# 3_-_SRAM.net
KiCad netlist of a schematic drawn in Altium Designer
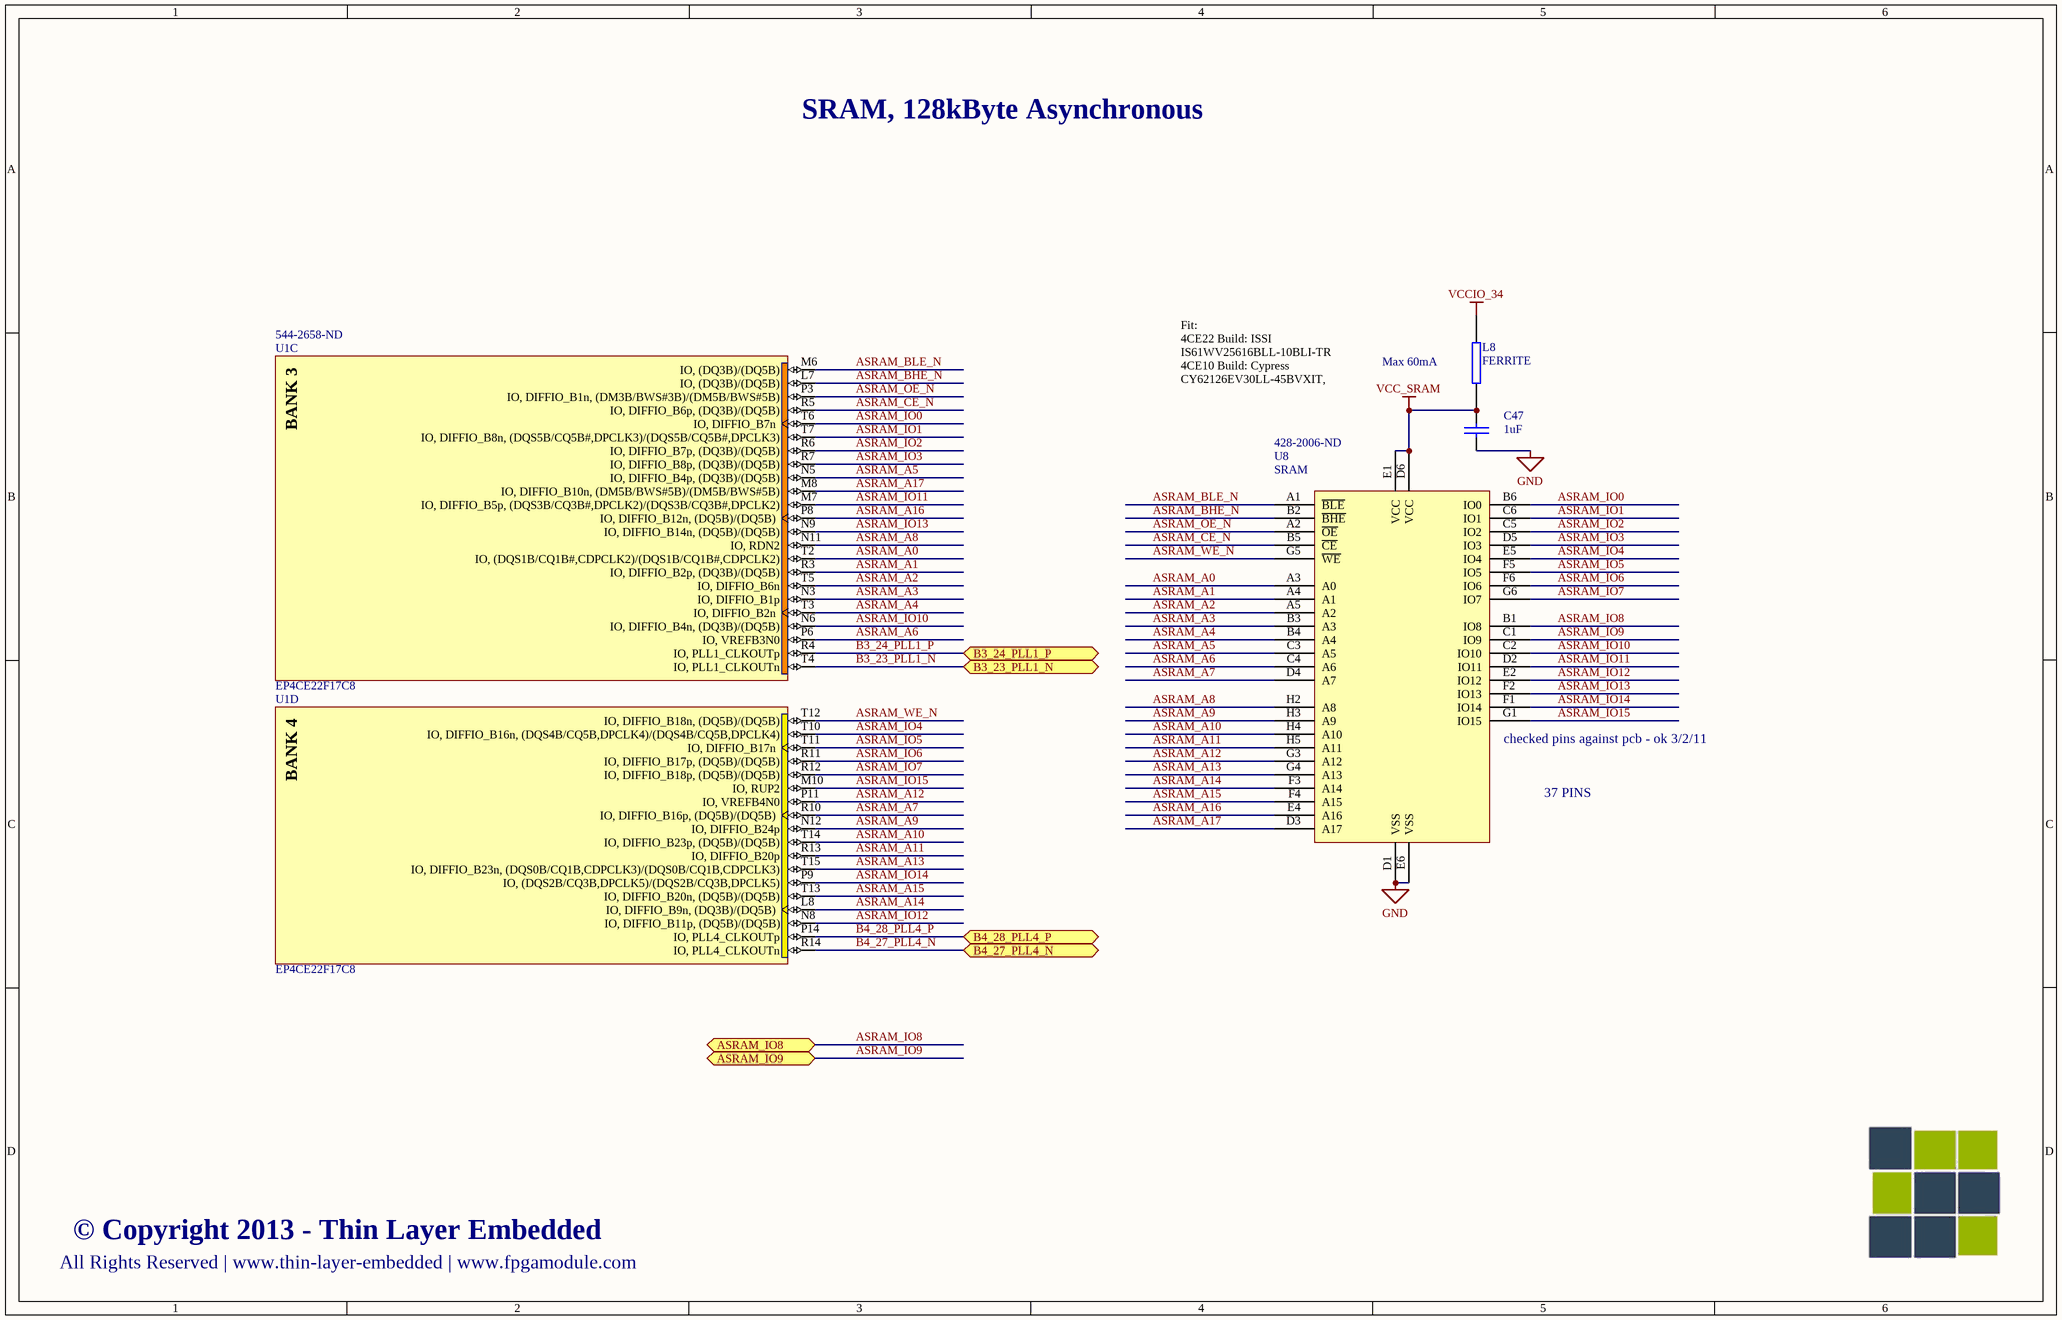
[diagram p0: 3 - SRAM.SchDoc]

(export (version "E")
  (design (tool "Eeschema 10.0.6"))
  (components
    (comp (ref "C47")
      (value "1uF")
      (footprint "0402_HD")
      (description "Capacitor")
      (fields
        (field (name "MANUFACTURER") "Yageo")
        (field (name "MANUFACTURER PART NUMBER") "CC0402ZRY5V8BB104")
      )
      (libsource (lib "*") (part "CAP"))
    )
    (comp (ref "L8") (value "FERRITE") (footprint "0402_HD") (libsource (lib "*") (part "FERRITE")))
    (comp (ref "U1")
      (value "EP4CE22F17C8")
      (footprint "FBGA256")
      (description "IC CYCLONE IV E FPGA 22K 256FBGA")
      (fields
        (field (name "SUPPLIER PART NUMBER 1") "544-2658-ND")
        (field (name "MANUFACTURER") "Altera")
        (field (name "MANUFACTURER PART NUMBER") "EP4CE22F17C7N")
        (field (name "PUBLISHER") "Altium Limited")
      )
      (libsource (lib "OB_EP4CE15E22") (part "EP4CE22F17C8"))
    )
    (comp (ref "U8")
      (value "SRAM")
      (footprint "VFBGA48")
      (description "IC SRAM 1MBIT 10NS 48VFBGA")
      (fields
        (field (name "SUPPLIER PART NUMBER 1") "428-2006-ND")
        (field (name "MANUFACTURER") "Cypress Semiconductor Corp")
        (field (name "MANUFACTURER PART NUMBER") "CY7C1021DV33-10BVXI")
      )
      (libsource (lib "OB_EP4CE15E22") (part "CY7C1021DV331"))
    )
  )
  (nets
    (net (code "1") (name "/ASRAM_A0") (class "Default")
      (node (ref "U1") (pin "T2") (pinfunction "IO,_(DQS1B/CQ1B#,CDPCLK2)/(DQS1B/CQ1B#,CDPCLK2)_T2") (pintype "bidirectional"))
      (node (ref "U8") (pin "A3") (pinfunction "A0_A3") (pintype "passive"))
    )
    (net (code "2") (name "/ASRAM_A1") (class "Default")
      (node (ref "U1") (pin "R3") (pinfunction "IO,_DIFFIO_B2p,_(DQ3B)/(DQ5B)_R3") (pintype "bidirectional"))
      (node (ref "U8") (pin "A4") (pinfunction "A1_A4") (pintype "passive"))
    )
    (net (code "3") (name "/ASRAM_A2") (class "Default")
      (node (ref "U1") (pin "T5") (pinfunction "IO,_DIFFIO_B6n_T5") (pintype "bidirectional"))
      (node (ref "U8") (pin "A5") (pinfunction "A2_A5") (pintype "passive"))
    )
    (net (code "4") (name "/ASRAM_A3") (class "Default")
      (node (ref "U1") (pin "N3") (pinfunction "IO,_DIFFIO_B1p_N3") (pintype "bidirectional"))
      (node (ref "U8") (pin "B3") (pinfunction "A3_B3") (pintype "passive"))
    )
    (net (code "5") (name "/ASRAM_A4") (class "Default")
      (node (ref "U1") (pin "T3") (pinfunction "IO,_DIFFIO_B2n_T3") (pintype "bidirectional"))
      (node (ref "U8") (pin "B4") (pinfunction "A4_B4") (pintype "passive"))
    )
    (net (code "6") (name "/ASRAM_A5") (class "Default")
      (node (ref "U1") (pin "N5") (pinfunction "IO,_DIFFIO_B4p,_(DQ3B)/(DQ5B)_N5") (pintype "bidirectional"))
      (node (ref "U8") (pin "C3") (pinfunction "A5_C3") (pintype "passive"))
    )
    (net (code "7") (name "/ASRAM_A6") (class "Default")
      (node (ref "U1") (pin "P6") (pinfunction "IO,_VREFB3N0_P6") (pintype "bidirectional"))
      (node (ref "U8") (pin "C4") (pinfunction "A6_C4") (pintype "passive"))
    )
    (net (code "8") (name "/ASRAM_A7") (class "Default")
      (node (ref "U1") (pin "R10") (pinfunction "IO,_DIFFIO_B16p,_(DQ5B)/(DQ5B)_R10") (pintype "bidirectional"))
      (node (ref "U8") (pin "D4") (pinfunction "A7_D4") (pintype "passive"))
    )
    (net (code "9") (name "/ASRAM_A8") (class "Default")
      (node (ref "U1") (pin "N11") (pinfunction "IO,_RDN2_N11") (pintype "bidirectional"))
      (node (ref "U8") (pin "H2") (pinfunction "A8_H2") (pintype "passive"))
    )
    (net (code "10") (name "/ASRAM_A9") (class "Default")
      (node (ref "U1") (pin "N12") (pinfunction "IO,_DIFFIO_B24p_N12") (pintype "bidirectional"))
      (node (ref "U8") (pin "H3") (pinfunction "A9_H3") (pintype "passive"))
    )
    (net (code "11") (name "/ASRAM_A10") (class "Default")
      (node (ref "U1") (pin "T14") (pinfunction "IO,_DIFFIO_B23p,_(DQ5B)/(DQ5B)_T14") (pintype "bidirectional"))
      (node (ref "U8") (pin "H4") (pinfunction "A10_H4") (pintype "passive"))
    )
    (net (code "12") (name "/ASRAM_A11") (class "Default")
      (node (ref "U1") (pin "R13") (pinfunction "IO,_DIFFIO_B20p_R13") (pintype "bidirectional"))
      (node (ref "U8") (pin "H5") (pinfunction "A11_H5") (pintype "passive"))
    )
    (net (code "13") (name "/ASRAM_A12") (class "Default")
      (node (ref "U1") (pin "P11") (pinfunction "IO,_VREFB4N0_P11") (pintype "bidirectional"))
      (node (ref "U8") (pin "G3") (pinfunction "A12_G3") (pintype "passive"))
    )
    (net (code "14") (name "/ASRAM_A13") (class "Default")
      (node (ref "U1") (pin "T15") (pinfunction "IO,_DIFFIO_B23n,_(DQS0B/CQ1B,CDPCLK3)/(DQS0B/CQ1B,CDPCLK3)_T15") (pintype "bidirectional"))
      (node (ref "U8") (pin "G4") (pinfunction "A13_G4") (pintype "passive"))
    )
    (net (code "15") (name "/ASRAM_A14") (class "Default")
      (node (ref "U1") (pin "L8") (pinfunction "IO,_DIFFIO_B9n,_(DQ3B)/(DQ5B)_L8") (pintype "bidirectional"))
      (node (ref "U8") (pin "F3") (pinfunction "A14_F3") (pintype "passive"))
    )
    (net (code "16") (name "/ASRAM_A15") (class "Default")
      (node (ref "U1") (pin "T13") (pinfunction "IO,_DIFFIO_B20n,_(DQ5B)/(DQ5B)_T13") (pintype "bidirectional"))
      (node (ref "U8") (pin "F4") (pinfunction "A15_F4") (pintype "passive"))
    )
    (net (code "17") (name "/ASRAM_A16") (class "Default")
      (node (ref "U1") (pin "P8") (pinfunction "IO,_DIFFIO_B12n,_(DQ5B)/(DQ5B)_P8") (pintype "bidirectional"))
      (node (ref "U8") (pin "E4") (pinfunction "A16_E4") (pintype "passive"))
    )
    (net (code "18") (name "/ASRAM_A17") (class "Default")
      (node (ref "U1") (pin "M8") (pinfunction "IO,_DIFFIO_B10n,_(DM5B/BWS#5B)/(DM5B/BWS#5B)_M8") (pintype "bidirectional"))
      (node (ref "U8") (pin "D3") (pinfunction "A17_D3") (pintype "passive"))
    )
    (net (code "19") (name "/ASRAM_BHE_N") (class "Default")
      (node (ref "U1") (pin "L7") (pinfunction "IO,_(DQ3B)/(DQ5B)_L7") (pintype "bidirectional"))
      (node (ref "U8") (pin "B2") (pinfunction "~{BHE}_B2") (pintype "passive"))
    )
    (net (code "20") (name "/ASRAM_BLE_N") (class "Default")
      (node (ref "U1") (pin "M6") (pinfunction "IO,_(DQ3B)/(DQ5B)_M6") (pintype "bidirectional"))
      (node (ref "U8") (pin "A1") (pinfunction "~{BLE}_A1") (pintype "passive"))
    )
    (net (code "21") (name "/ASRAM_CE_N") (class "Default")
      (node (ref "U1") (pin "R5") (pinfunction "IO,_DIFFIO_B6p,_(DQ3B)/(DQ5B)_R5") (pintype "bidirectional"))
      (node (ref "U8") (pin "B5") (pinfunction "~{CE}_B5") (pintype "passive"))
    )
    (net (code "22") (name "/ASRAM_IO0") (class "Default")
      (node (ref "U1") (pin "T6") (pinfunction "IO,_DIFFIO_B7n_T6") (pintype "bidirectional"))
      (node (ref "U8") (pin "B6") (pinfunction "IO0_B6") (pintype "passive"))
    )
    (net (code "23") (name "/ASRAM_IO1") (class "Default")
      (node (ref "U1") (pin "T7") (pinfunction "IO,_DIFFIO_B8n,_(DQS5B/CQ5B#,DPCLK3)/(DQS5B/CQ5B#,DPCLK3)_T7") (pintype "bidirectional"))
      (node (ref "U8") (pin "C6") (pinfunction "IO1_C6") (pintype "passive"))
    )
    (net (code "24") (name "/ASRAM_IO2") (class "Default")
      (node (ref "U1") (pin "R6") (pinfunction "IO,_DIFFIO_B7p,_(DQ3B)/(DQ5B)_R6") (pintype "bidirectional"))
      (node (ref "U8") (pin "C5") (pinfunction "IO2_C5") (pintype "passive"))
    )
    (net (code "25") (name "/ASRAM_IO3") (class "Default")
      (node (ref "U1") (pin "R7") (pinfunction "IO,_DIFFIO_B8p,_(DQ3B)/(DQ5B)_R7") (pintype "bidirectional"))
      (node (ref "U8") (pin "D5") (pinfunction "IO3_D5") (pintype "passive"))
    )
    (net (code "26") (name "/ASRAM_IO4") (class "Default")
      (node (ref "U1") (pin "T10") (pinfunction "IO,_DIFFIO_B16n,_(DQS4B/CQ5B,DPCLK4)/(DQS4B/CQ5B,DPCLK4)_T10") (pintype "bidirectional"))
      (node (ref "U8") (pin "E5") (pinfunction "IO4_E5") (pintype "passive"))
    )
    (net (code "27") (name "/ASRAM_IO5") (class "Default")
      (node (ref "U1") (pin "T11") (pinfunction "IO,_DIFFIO_B17n_T11") (pintype "bidirectional"))
      (node (ref "U8") (pin "F5") (pinfunction "IO5_F5") (pintype "passive"))
    )
    (net (code "28") (name "/ASRAM_IO6") (class "Default")
      (node (ref "U1") (pin "R11") (pinfunction "IO,_DIFFIO_B17p,_(DQ5B)/(DQ5B)_R11") (pintype "bidirectional"))
      (node (ref "U8") (pin "F6") (pinfunction "IO6_F6") (pintype "passive"))
    )
    (net (code "29") (name "/ASRAM_IO7") (class "Default")
      (node (ref "U1") (pin "R12") (pinfunction "IO,_DIFFIO_B18p,_(DQ5B)/(DQ5B)_R12") (pintype "bidirectional"))
      (node (ref "U8") (pin "G6") (pinfunction "IO7_G6") (pintype "passive"))
    )
    (net (code "30") (name "/ASRAM_IO8") (class "Default")
      (node (ref "U8") (pin "B1") (pinfunction "IO8_B1") (pintype "passive"))
    )
    (net (code "31") (name "/ASRAM_IO9") (class "Default")
      (node (ref "U8") (pin "C1") (pinfunction "IO9_C1") (pintype "passive"))
    )
    (net (code "32") (name "/ASRAM_IO10") (class "Default")
      (node (ref "U1") (pin "N6") (pinfunction "IO,_DIFFIO_B4n,_(DQ3B)/(DQ5B)_N6") (pintype "bidirectional"))
      (node (ref "U8") (pin "C2") (pinfunction "IO10_C2") (pintype "passive"))
    )
    (net (code "33") (name "/ASRAM_IO11") (class "Default")
      (node (ref "U1") (pin "M7") (pinfunction "IO,_DIFFIO_B5p,_(DQS3B/CQ3B#,DPCLK2)/(DQS3B/CQ3B#,DPCLK2)_M7") (pintype "bidirectional"))
      (node (ref "U8") (pin "D2") (pinfunction "IO11_D2") (pintype "passive"))
    )
    (net (code "34") (name "/ASRAM_IO12") (class "Default")
      (node (ref "U1") (pin "N8") (pinfunction "IO,_DIFFIO_B11p,_(DQ5B)/(DQ5B)_N8") (pintype "bidirectional"))
      (node (ref "U8") (pin "E2") (pinfunction "IO12_E2") (pintype "passive"))
    )
    (net (code "35") (name "/ASRAM_IO13") (class "Default")
      (node (ref "U1") (pin "N9") (pinfunction "IO,_DIFFIO_B14n,_(DQ5B)/(DQ5B)_N9") (pintype "bidirectional"))
      (node (ref "U8") (pin "F2") (pinfunction "IO13_F2") (pintype "passive"))
    )
    (net (code "36") (name "/ASRAM_IO14") (class "Default")
      (node (ref "U1") (pin "P9") (pinfunction "IO,_(DQS2B/CQ3B,DPCLK5)/(DQS2B/CQ3B,DPCLK5)_P9") (pintype "bidirectional"))
      (node (ref "U8") (pin "F1") (pinfunction "IO14_F1") (pintype "passive"))
    )
    (net (code "37") (name "/ASRAM_IO15") (class "Default")
      (node (ref "U1") (pin "M10") (pinfunction "IO,_RUP2_M10") (pintype "bidirectional"))
      (node (ref "U8") (pin "G1") (pinfunction "IO15_G1") (pintype "passive"))
    )
    (net (code "38") (name "/ASRAM_OE_N") (class "Default")
      (node (ref "U1") (pin "P3") (pinfunction "IO,_DIFFIO_B1n,_(DM3B/BWS#3B)/(DM5B/BWS#5B)_P3") (pintype "bidirectional"))
      (node (ref "U8") (pin "A2") (pinfunction "~{OE}_A2") (pintype "passive"))
    )
    (net (code "39") (name "/ASRAM_WE_N") (class "Default")
      (node (ref "U1") (pin "T12") (pinfunction "IO,_DIFFIO_B18n,_(DQ5B)/(DQ5B)_T12") (pintype "bidirectional"))
      (node (ref "U8") (pin "G5") (pinfunction "~{WE}_G5") (pintype "passive"))
    )
    (net (code "40") (name "/B3_23_PLL1_N") (class "Default")
      (node (ref "U1") (pin "T4") (pinfunction "IO,_PLL1_CLKOUTn_T4") (pintype "bidirectional"))
    )
    (net (code "41") (name "/B3_24_PLL1_P") (class "Default")
      (node (ref "U1") (pin "R4") (pinfunction "IO,_PLL1_CLKOUTp_R4") (pintype "bidirectional"))
    )
    (net (code "42") (name "/B4_27_PLL4_N") (class "Default")
      (node (ref "U1") (pin "R14") (pinfunction "IO,_PLL4_CLKOUTn_R14") (pintype "bidirectional"))
    )
    (net (code "43") (name "/B4_28_PLL4_P") (class "Default")
      (node (ref "U1") (pin "P14") (pinfunction "IO,_PLL4_CLKOUTp_P14") (pintype "bidirectional"))
    )
    (net (code "44") (name "GND") (class "Default")
      (node (ref "C47") (pin "2") (pinfunction "2_2") (pintype "passive"))
      (node (ref "U8") (pin "D1") (pinfunction "VSS_D1") (pintype "passive"))
      (node (ref "U8") (pin "E6") (pinfunction "VSS_E6") (pintype "passive"))
    )
    (net (code "45") (name "VCCIO_34") (class "Default")
      (node (ref "L8") (pin "2") (pinfunction "2_2") (pintype "passive"))
    )
    (net (code "46") (name "VCC_SRAM") (class "Default")
      (node (ref "C47") (pin "1") (pinfunction "1_1") (pintype "passive"))
      (node (ref "L8") (pin "1") (pinfunction "1_1") (pintype "passive"))
      (node (ref "U8") (pin "D6") (pinfunction "VCC_D6") (pintype "passive"))
      (node (ref "U8") (pin "E1") (pinfunction "VCC_E1") (pintype "passive"))
    )
  )
)
